# SCH_depth-sensor_2025-08-24.net
KiCad netlist of a schematic drawn in EasyEDA
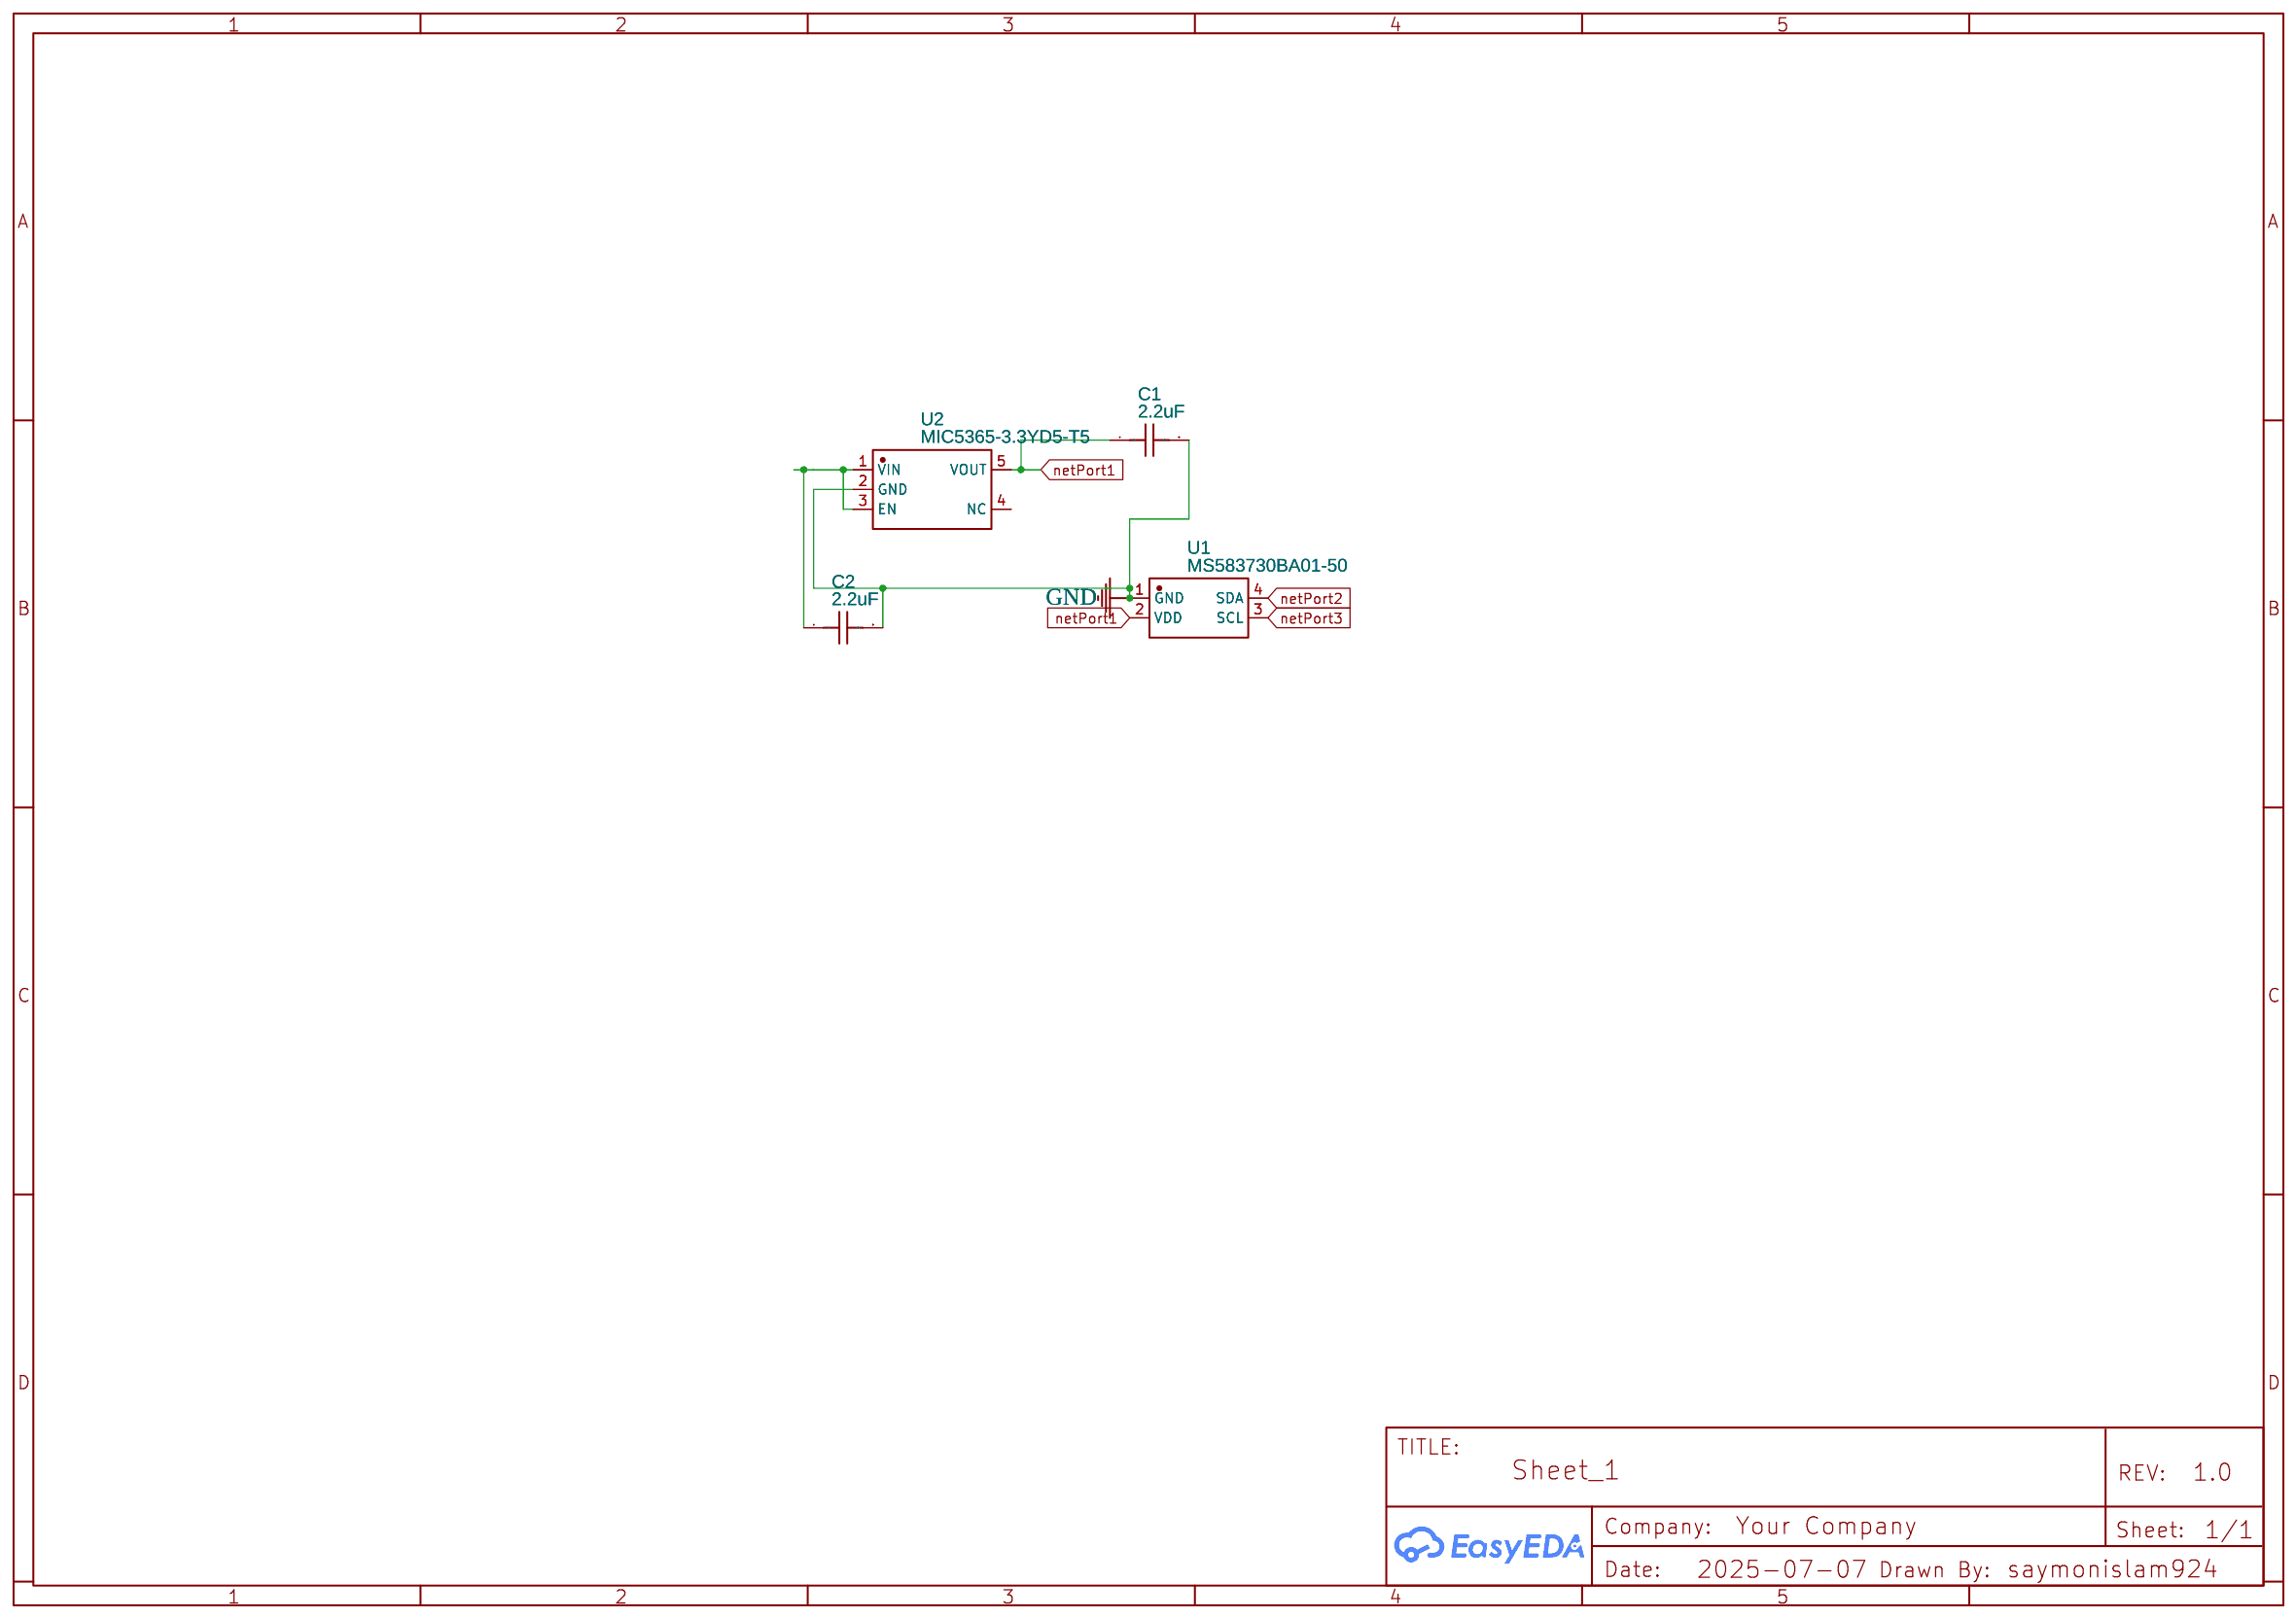
[diagram p0: schematic sheet]

(export (version "E")
  (design (tool "Eeschema 10.0.6"))
  (components
    (comp (ref "C1")
      (value "2.2uF")
      (fields
        (field (name "Manufacturer Part") "CC0603KRX7R5BB225")
        (field (name "Manufacturer") "YAGEO(国巨)")
      )
      (libsource (lib "") (part "CC0603KRX7R5BB225"))
    )
    (comp (ref "C2")
      (value "2.2uF")
      (fields
        (field (name "Manufacturer Part") "CC0603KRX7R5BB225")
        (field (name "Manufacturer") "YAGEO(国巨)")
      )
      (libsource (lib "") (part "CC0603KRX7R5BB225"))
    )
    (comp (ref "U1")
      (value "MS583730BA01-50")
      (fields (field (name "Manufacturer") "TE Connectivity(泰科电子)"))
      (libsource (lib "") (part "MS583730BA01-50"))
    )
    (comp (ref "U2")
      (value "MIC5365-3.3YD5-T5")
      (fields (field (name "Manufacturer") "MICROCHIP(美国微芯)"))
      (libsource (lib "") (part "MIC5365-3.3YD5-T5"))
    )
  )
  (nets
    (net (code "1") (name "GND") (class "Default")
      (node (ref "C1") (pin "2") (pinfunction "2_2") (pintype "unspecified"))
      (node (ref "C2") (pin "2") (pinfunction "2_2") (pintype "unspecified"))
      (node (ref "U1") (pin "1") (pinfunction "GND_1") (pintype "unspecified"))
      (node (ref "U2") (pin "2") (pinfunction "GND_2") (pintype "unspecified"))
    )
    (net (code "2") (name "Net-(U2-EN)") (class "Default")
      (node (ref "C2") (pin "1") (pinfunction "1_1") (pintype "unspecified"))
      (node (ref "U2") (pin "1") (pinfunction "VIN_1") (pintype "unspecified"))
      (node (ref "U2") (pin "3") (pinfunction "EN_3") (pintype "unspecified"))
    )
    (net (code "3") (name "netPort1") (class "Default")
      (node (ref "C1") (pin "1") (pinfunction "1_1") (pintype "unspecified"))
      (node (ref "U1") (pin "2") (pinfunction "VDD_2") (pintype "unspecified"))
      (node (ref "U2") (pin "5") (pinfunction "VOUT_5") (pintype "unspecified"))
    )
    (net (code "4") (name "netPort2") (class "Default")
      (node (ref "U1") (pin "4") (pinfunction "SDA_4") (pintype "unspecified"))
    )
    (net (code "5") (name "netPort3") (class "Default")
      (node (ref "U1") (pin "3") (pinfunction "SCL_3") (pintype "unspecified"))
    )
    (net (code "6") (name "unconnected-(U2-NC-Pad4)") (class "Default")
      (node (ref "U2") (pin "4") (pinfunction "NC_4") (pintype "unspecified"))
    )
  )
)
